# COMMUNICATION.net
KiCad netlist of a schematic drawn in Altium Designer
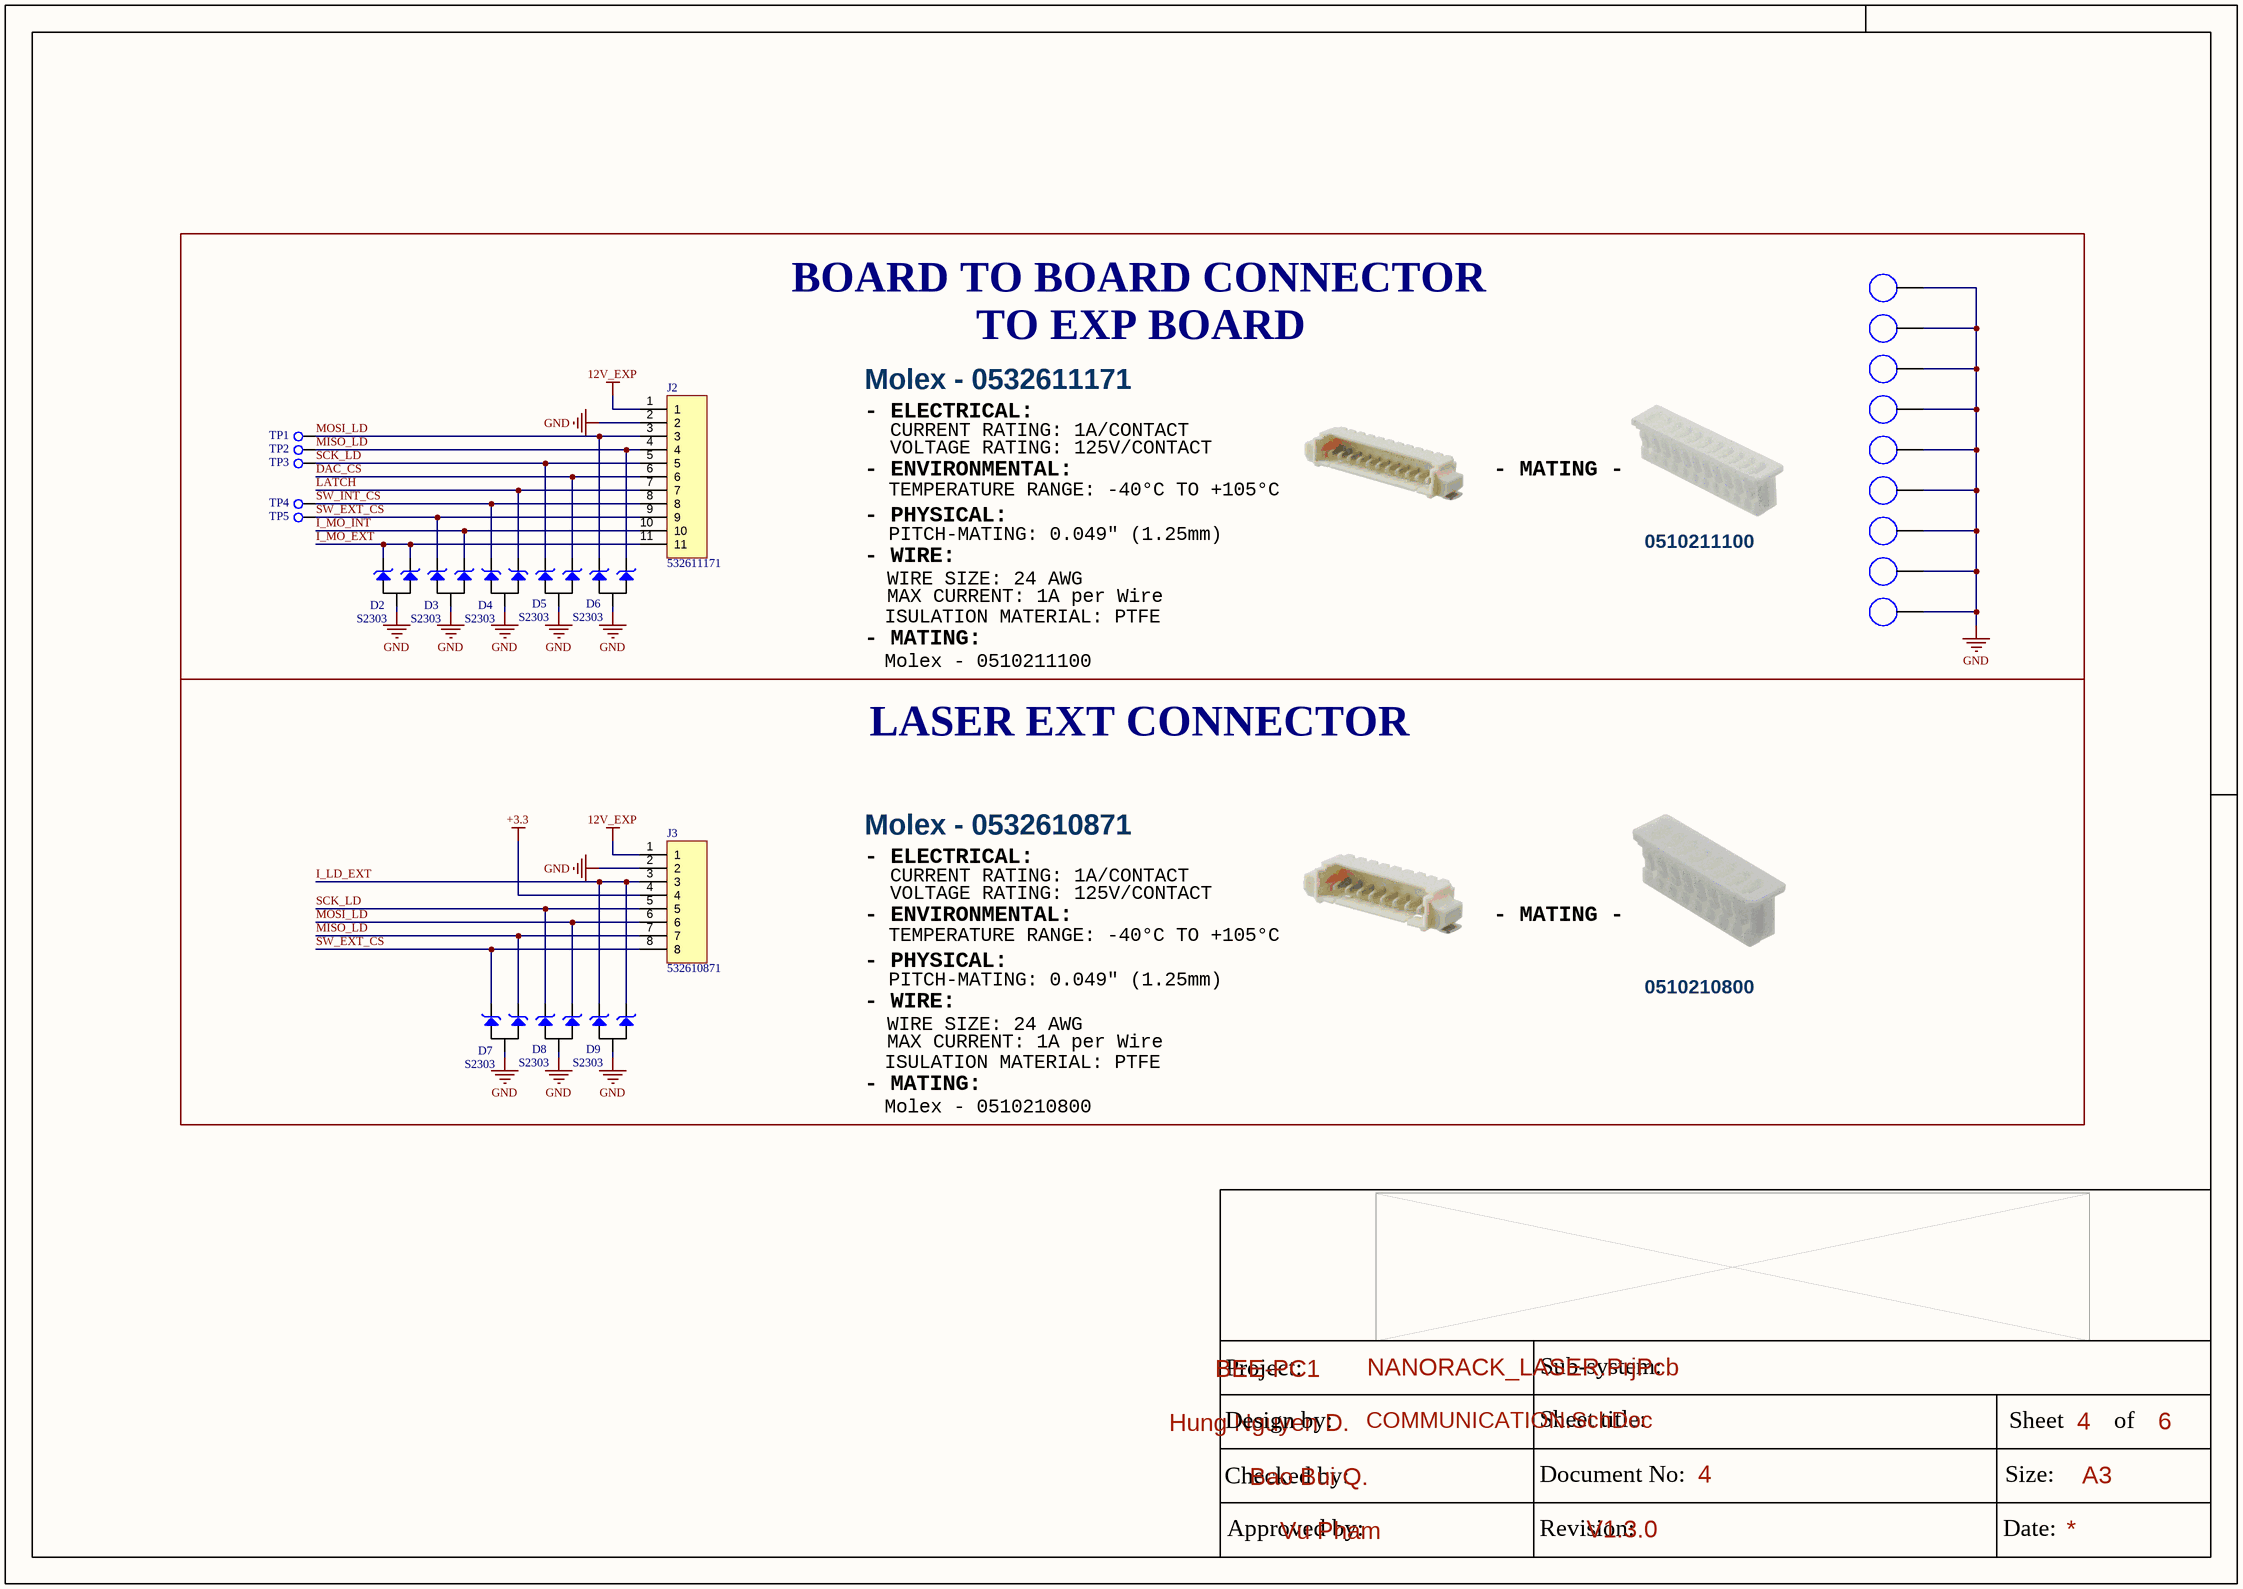
[diagram p0: COMMUNICATION.SchDoc]

(export (version "E")
  (design (tool "Eeschema 10.0.6"))
  (components
    (comp (ref "D2") (value "S2303") (footprint "SOT23-123") (libsource (lib "Library") (part "S2303")))
    (comp (ref "D3") (value "S2303") (footprint "SOT23-123") (libsource (lib "Library") (part "S2303")))
    (comp (ref "D4") (value "S2303") (footprint "SOT23-123") (libsource (lib "Library") (part "S2303")))
    (comp (ref "D5") (value "S2303") (footprint "SOT23-123") (libsource (lib "Library") (part "S2303")))
    (comp (ref "D6") (value "S2303") (footprint "SOT23-123") (libsource (lib "Library") (part "S2303")))
    (comp (ref "D7") (value "S2303") (footprint "SOT23-123") (libsource (lib "Library") (part "S2303")))
    (comp (ref "D8") (value "S2303") (footprint "SOT23-123") (libsource (lib "Library") (part "S2303")))
    (comp (ref "D9") (value "S2303") (footprint "SOT23-123") (libsource (lib "Library") (part "S2303")))
    (comp (ref "H1") (value "HOLD") (footprint "M3") (libsource (lib "Library_HUNG") (part "PAD_HOLD")))
    (comp (ref "H2") (value "HOLD") (footprint "M3") (libsource (lib "Library_HUNG") (part "PAD_HOLD")))
    (comp (ref "H3") (value "HOLD") (footprint "M3") (libsource (lib "Library_HUNG") (part "PAD_HOLD")))
    (comp (ref "H4") (value "HOLD") (footprint "M3") (libsource (lib "Library_HUNG") (part "PAD_HOLD")))
    (comp (ref "H5") (value "HOLD") (footprint "M3") (libsource (lib "Library_HUNG") (part "PAD_HOLD")))
    (comp (ref "H6") (value "HOLD") (footprint "M3") (libsource (lib "Library_HUNG") (part "PAD_HOLD")))
    (comp (ref "H7") (value "HOLD") (footprint "M3") (libsource (lib "Library_HUNG") (part "PAD_HOLD")))
    (comp (ref "H8") (value "HOLD") (footprint "M3") (libsource (lib "Library_HUNG") (part "PAD_HOLD")))
    (comp (ref "H9") (value "HOLD") (footprint "M3") (libsource (lib "Library_HUNG") (part "PAD_HOLD")))
    (comp (ref "J2")
      (value "532611171")
      (footprint "MOLEX_532611171")
      (fields (field (name "COPYRIGHT") "Copyright (C) 2025 Ultra Librarian. All rights reserved."))
      (libsource (lib "DAK_Altium_Integrated_Lib") (part "532611171"))
    )
    (comp (ref "J3")
      (value "532610871")
      (footprint "MOLEX_532610001")
      (fields (field (name "COPYRIGHT") "Copyright (C) 2025 Ultra Librarian. All rights reserved."))
      (libsource (lib "DAK_Altium_Integrated_Lib") (part "532610871"))
    )
    (comp (ref "TP1")
      (value "Test_Point")
      (footprint "TESTPOINT")
      (libsource (lib "Library_HUNG") (part "Test_Point"))
    )
    (comp (ref "TP2")
      (value "Test_Point")
      (footprint "TESTPOINT")
      (libsource (lib "Library_HUNG") (part "Test_Point"))
    )
    (comp (ref "TP3")
      (value "Test_Point")
      (footprint "TESTPOINT")
      (libsource (lib "Library_HUNG") (part "Test_Point"))
    )
    (comp (ref "TP4")
      (value "Test_Point")
      (footprint "TESTPOINT")
      (libsource (lib "Library_HUNG") (part "Test_Point"))
    )
    (comp (ref "TP5")
      (value "Test_Point")
      (footprint "TESTPOINT")
      (libsource (lib "Library_HUNG") (part "Test_Point"))
    )
  )
  (nets
    (net (code "1") (name "+3.3") (class "Default")
      (node (ref "J3") (pin "4") (pinfunction "4_4") (pintype "passive"))
    )
    (net (code "2") (name "/DAC_CS") (class "Default")
      (node (ref "D5") (pin "3") (pintype "passive"))
      (node (ref "J2") (pin "6") (pinfunction "6_6") (pintype "passive"))
    )
    (net (code "3") (name "/I_LD_EXT") (class "Default")
      (node (ref "D9") (pin "1") (pintype "passive"))
      (node (ref "D9") (pin "3") (pintype "passive"))
      (node (ref "J3") (pin "3") (pinfunction "3_3") (pintype "passive"))
    )
    (net (code "4") (name "/I_MO_EXT") (class "Default")
      (node (ref "D2") (pin "1") (pintype "passive"))
      (node (ref "D2") (pin "3") (pintype "passive"))
      (node (ref "J2") (pin "11") (pinfunction "11_11") (pintype "passive"))
    )
    (net (code "5") (name "/I_MO_INT") (class "Default")
      (node (ref "D3") (pin "3") (pintype "passive"))
      (node (ref "J2") (pin "10") (pinfunction "10_10") (pintype "passive"))
    )
    (net (code "6") (name "/LATCH") (class "Default")
      (node (ref "D4") (pin "1") (pintype "passive"))
      (node (ref "J2") (pin "7") (pinfunction "7_7") (pintype "passive"))
    )
    (net (code "7") (name "/MISO_LD") (class "Default")
      (node (ref "D6") (pin "3") (pintype "passive"))
      (node (ref "D7") (pin "1") (pintype "passive"))
      (node (ref "J2") (pin "4") (pinfunction "4_4") (pintype "passive"))
      (node (ref "J3") (pin "7") (pinfunction "7_7") (pintype "passive"))
      (node (ref "TP2") (pin "1") (pintype "power_in"))
    )
    (net (code "8") (name "/MOSI_LD") (class "Default")
      (node (ref "D6") (pin "1") (pintype "passive"))
      (node (ref "D8") (pin "3") (pintype "passive"))
      (node (ref "J2") (pin "3") (pinfunction "3_3") (pintype "passive"))
      (node (ref "J3") (pin "6") (pinfunction "6_6") (pintype "passive"))
      (node (ref "TP1") (pin "1") (pintype "power_in"))
    )
    (net (code "9") (name "/SCK_LD") (class "Default")
      (node (ref "D5") (pin "1") (pintype "passive"))
      (node (ref "D8") (pin "1") (pintype "passive"))
      (node (ref "J2") (pin "5") (pinfunction "5_5") (pintype "passive"))
      (node (ref "J3") (pin "5") (pinfunction "5_5") (pintype "passive"))
      (node (ref "TP3") (pin "1") (pintype "power_in"))
    )
    (net (code "10") (name "/SW_EXT_CS") (class "Default")
      (node (ref "D3") (pin "1") (pintype "passive"))
      (node (ref "D7") (pin "3") (pintype "passive"))
      (node (ref "J2") (pin "9") (pinfunction "9_9") (pintype "passive"))
      (node (ref "J3") (pin "8") (pinfunction "8_8") (pintype "passive"))
      (node (ref "TP5") (pin "1") (pintype "power_in"))
    )
    (net (code "11") (name "/SW_INT_CS") (class "Default")
      (node (ref "D4") (pin "3") (pintype "passive"))
      (node (ref "J2") (pin "8") (pinfunction "8_8") (pintype "passive"))
      (node (ref "TP4") (pin "1") (pintype "power_in"))
    )
    (net (code "12") (name "12V_EXP") (class "Default")
      (node (ref "J2") (pin "1") (pinfunction "1_1") (pintype "passive"))
      (node (ref "J3") (pin "1") (pinfunction "1_1") (pintype "passive"))
    )
    (net (code "13") (name "GND") (class "Default")
      (node (ref "D2") (pin "2") (pintype "passive"))
      (node (ref "D3") (pin "2") (pintype "passive"))
      (node (ref "D4") (pin "2") (pintype "passive"))
      (node (ref "D5") (pin "2") (pintype "passive"))
      (node (ref "D6") (pin "2") (pintype "passive"))
      (node (ref "D7") (pin "2") (pintype "passive"))
      (node (ref "D8") (pin "2") (pintype "passive"))
      (node (ref "D9") (pin "2") (pintype "passive"))
      (node (ref "H1") (pin "1") (pintype "power_in"))
      (node (ref "H2") (pin "1") (pintype "power_in"))
      (node (ref "H3") (pin "1") (pintype "power_in"))
      (node (ref "H4") (pin "1") (pintype "power_in"))
      (node (ref "H5") (pin "1") (pintype "power_in"))
      (node (ref "H6") (pin "1") (pintype "power_in"))
      (node (ref "H7") (pin "1") (pintype "power_in"))
      (node (ref "H8") (pin "1") (pintype "power_in"))
      (node (ref "H9") (pin "1") (pintype "power_in"))
      (node (ref "J2") (pin "2") (pinfunction "2_2") (pintype "passive"))
      (node (ref "J3") (pin "2") (pinfunction "2_2") (pintype "passive"))
    )
  )
)
